# SensorModule.net
KiCad netlist of a schematic drawn in EAGLE
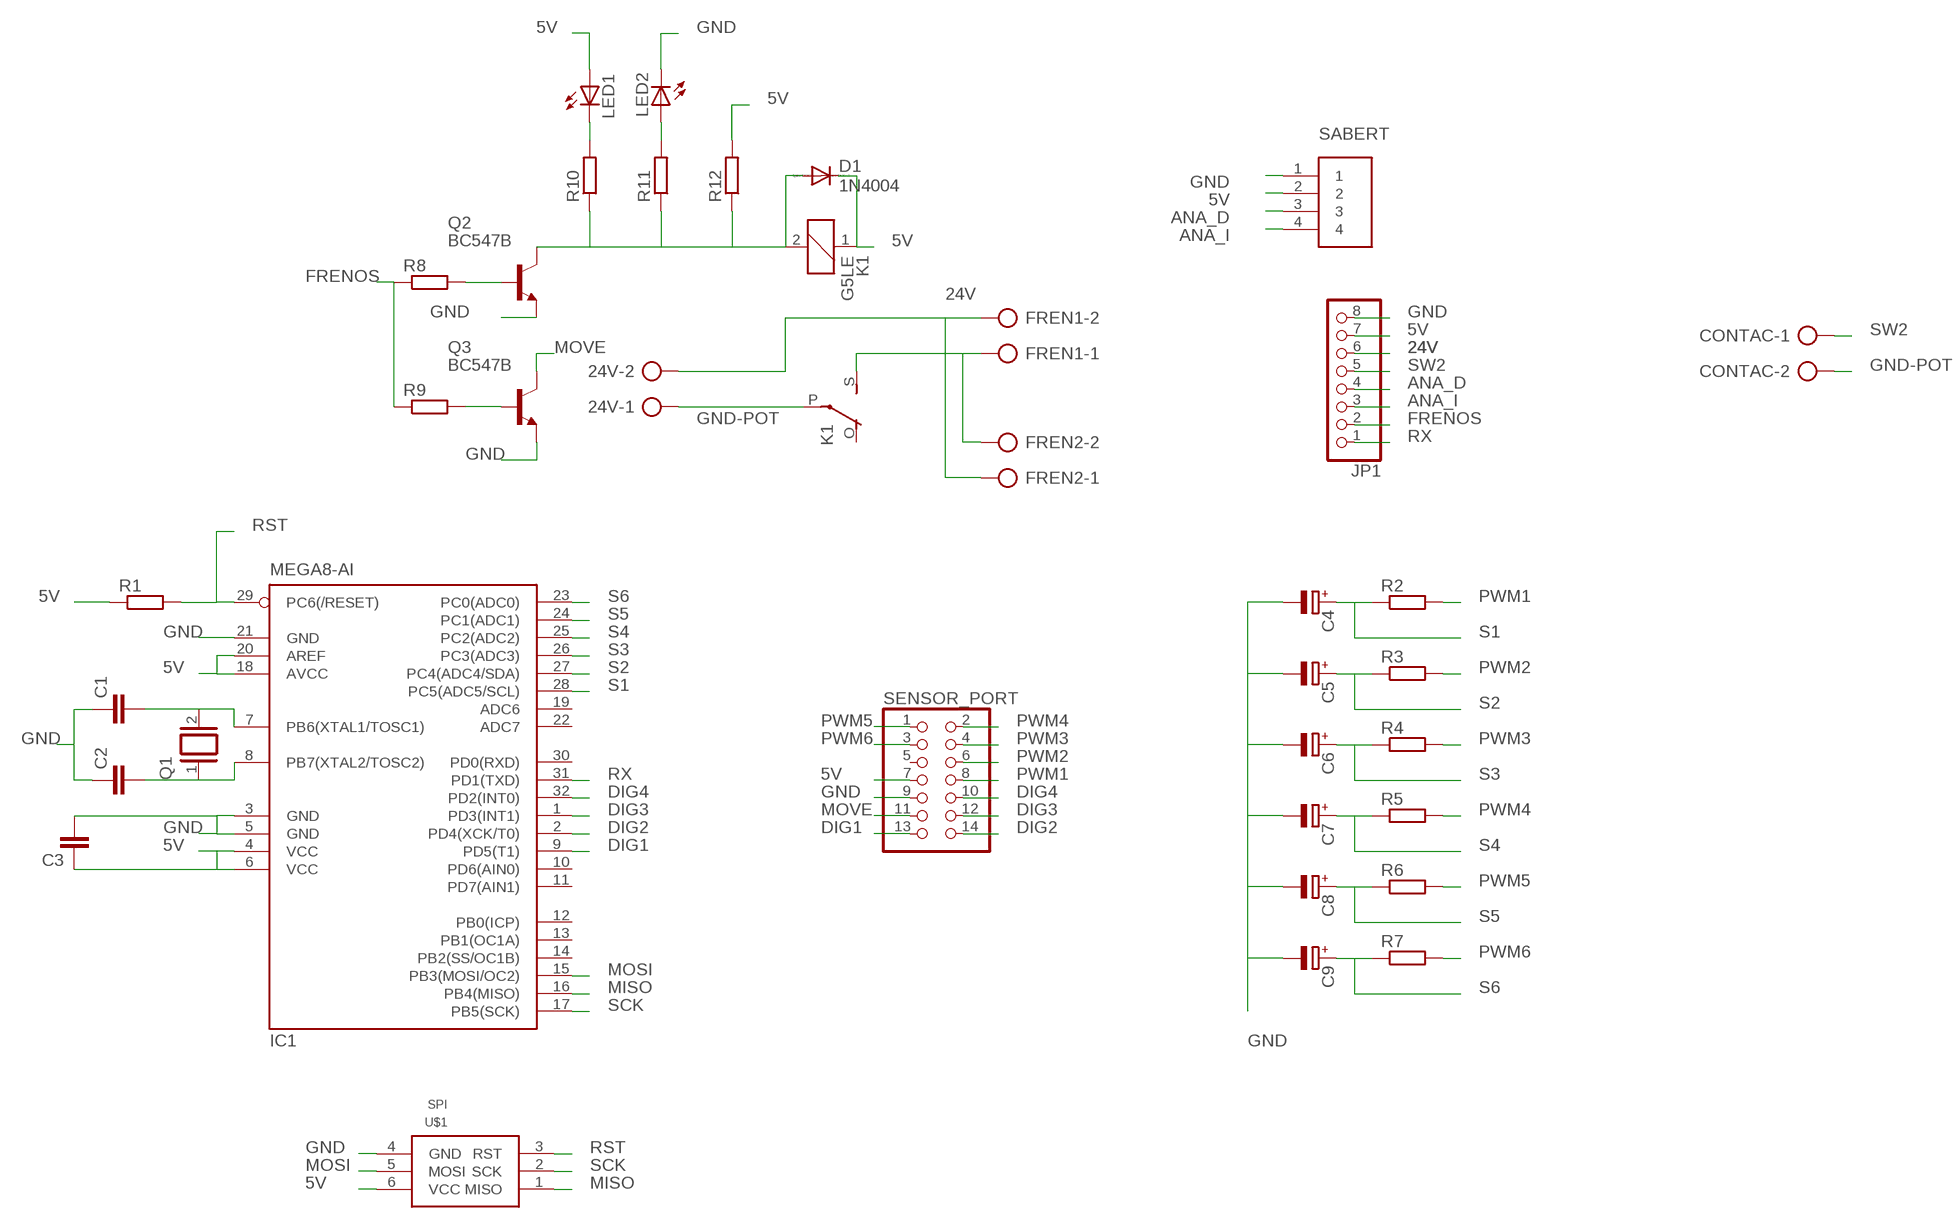
[diagram p0: schematic, sheet 1]

(export (version "E")
  (design (tool "Eeschema 10.0.6"))
  (components
    (comp (ref "24V")
      (value "AK500/2")
      (footprint "eagle-import:AK500_2")
      (libsource (lib "eagle-import") (part "AK500/2"))
    )
    (comp (ref "C1")
      (value "C-EUC0402K")
      (footprint "eagle-import:C0402K")
      (libsource (lib "eagle-import") (part "C-EUC0402K"))
    )
    (comp (ref "C2")
      (value "C-EUC0402K")
      (footprint "eagle-import:C0402K")
      (libsource (lib "eagle-import") (part "C-EUC0402K"))
    )
    (comp (ref "C3")
      (value "C-EUC0402K")
      (footprint "eagle-import:C0402K")
      (libsource (lib "eagle-import") (part "C-EUC0402K"))
    )
    (comp (ref "C4")
      (value "CPOL-EU153CLV-0505")
      (footprint "eagle-import:153CLV-0505")
      (libsource (lib "eagle-import") (part "CPOL-EU153CLV-0505"))
    )
    (comp (ref "C5")
      (value "CPOL-EU153CLV-0505")
      (footprint "eagle-import:153CLV-0505")
      (libsource (lib "eagle-import") (part "CPOL-EU153CLV-0505"))
    )
    (comp (ref "C6")
      (value "CPOL-EU153CLV-0505")
      (footprint "eagle-import:153CLV-0505")
      (libsource (lib "eagle-import") (part "CPOL-EU153CLV-0505"))
    )
    (comp (ref "C7")
      (value "CPOL-EU153CLV-0505")
      (footprint "eagle-import:153CLV-0505")
      (libsource (lib "eagle-import") (part "CPOL-EU153CLV-0505"))
    )
    (comp (ref "C8")
      (value "CPOL-EU153CLV-0505")
      (footprint "eagle-import:153CLV-0505")
      (libsource (lib "eagle-import") (part "CPOL-EU153CLV-0505"))
    )
    (comp (ref "C9")
      (value "CPOL-EU153CLV-0505")
      (footprint "eagle-import:153CLV-0505")
      (libsource (lib "eagle-import") (part "CPOL-EU153CLV-0505"))
    )
    (comp (ref "CONTAC")
      (value "AK500/2")
      (footprint "eagle-import:AK500_2")
      (libsource (lib "eagle-import") (part "AK500/2"))
    )
    (comp (ref "D1")
      (value "1N4004")
      (footprint "eagle-import:DO41-10")
      (libsource (lib "eagle-import") (part "1N4004"))
    )
    (comp (ref "FREN1")
      (value "AK500/2")
      (footprint "eagle-import:AK500_2")
      (libsource (lib "eagle-import") (part "AK500/2"))
    )
    (comp (ref "FREN2")
      (value "AK500/2")
      (footprint "eagle-import:AK500_2")
      (libsource (lib "eagle-import") (part "AK500/2"))
    )
    (comp (ref "IC1")
      (value "MEGA8-AI")
      (footprint "eagle-import:TQFP32-08")
      (fields (field (name "MPN") "ATMEGA8-16AU"))
      (libsource (lib "eagle-import") (part "MEGA8-AI"))
    )
    (comp (ref "JP1")
      (value "PINHD-1X8")
      (footprint "eagle-import:1X08")
      (libsource (lib "eagle-import") (part "PINHD-1X8"))
    )
    (comp (ref "K1")
      (value "G5LE")
      (footprint "eagle-import:G5LE")
      (libsource (lib "eagle-import") (part "G5LE"))
    )
    (comp (ref "LED1")
      (value "LEDCHIP-LED0603")
      (footprint "eagle-import:CHIP-LED0603")
      (libsource (lib "eagle-import") (part "LEDCHIP-LED0603"))
    )
    (comp (ref "LED2")
      (value "LEDCHIP-LED0603")
      (footprint "eagle-import:CHIP-LED0603")
      (libsource (lib "eagle-import") (part "LEDCHIP-LED0603"))
    )
    (comp (ref "Q1")
      (value "XTAL/S")
      (footprint "eagle-import:QS")
      (libsource (lib "eagle-import") (part "XTAL/S"))
    )
    (comp (ref "Q2")
      (value "BC547B")
      (footprint "eagle-import:TO92")
      (libsource (lib "eagle-import") (part "BC547B"))
    )
    (comp (ref "Q3")
      (value "BC547B")
      (footprint "eagle-import:TO92")
      (libsource (lib "eagle-import") (part "BC547B"))
    )
    (comp (ref "R1")
      (value "R-EU_M1206")
      (footprint "eagle-import:M1206")
      (libsource (lib "eagle-import") (part "R-EU_M1206"))
    )
    (comp (ref "R2")
      (value "R-EU_M1206")
      (footprint "eagle-import:M1206")
      (libsource (lib "eagle-import") (part "R-EU_M1206"))
    )
    (comp (ref "R3")
      (value "R-EU_M1206")
      (footprint "eagle-import:M1206")
      (libsource (lib "eagle-import") (part "R-EU_M1206"))
    )
    (comp (ref "R4")
      (value "R-EU_M1206")
      (footprint "eagle-import:M1206")
      (libsource (lib "eagle-import") (part "R-EU_M1206"))
    )
    (comp (ref "R5")
      (value "R-EU_M1206")
      (footprint "eagle-import:M1206")
      (libsource (lib "eagle-import") (part "R-EU_M1206"))
    )
    (comp (ref "R6")
      (value "R-EU_M1206")
      (footprint "eagle-import:M1206")
      (libsource (lib "eagle-import") (part "R-EU_M1206"))
    )
    (comp (ref "R7")
      (value "R-EU_M1206")
      (footprint "eagle-import:M1206")
      (libsource (lib "eagle-import") (part "R-EU_M1206"))
    )
    (comp (ref "R8")
      (value "R-EU_M1206")
      (footprint "eagle-import:M1206")
      (libsource (lib "eagle-import") (part "R-EU_M1206"))
    )
    (comp (ref "R9")
      (value "R-EU_M1206")
      (footprint "eagle-import:M1206")
      (libsource (lib "eagle-import") (part "R-EU_M1206"))
    )
    (comp (ref "R10")
      (value "R-EU_M1206")
      (footprint "eagle-import:M1206")
      (libsource (lib "eagle-import") (part "R-EU_M1206"))
    )
    (comp (ref "R11")
      (value "R-EU_M1206")
      (footprint "eagle-import:M1206")
      (libsource (lib "eagle-import") (part "R-EU_M1206"))
    )
    (comp (ref "R12")
      (value "R-EU_M1206")
      (footprint "eagle-import:M1206")
      (libsource (lib "eagle-import") (part "R-EU_M1206"))
    )
    (comp (ref "SABERT")
      (value "CP2_1X4")
      (footprint "eagle-import:CP2_1X4")
      (libsource (lib "eagle-import") (part "CP2_1X4"))
    )
    (comp (ref "SENSOR_PORT")
      (value "PINHD-2X7")
      (footprint "eagle-import:2X07")
      (libsource (lib "eagle-import") (part "PINHD-2X7"))
    )
    (comp (ref "U$1")
      (value "SPI")
      (footprint "eagle-import:HEAD-2X3")
      (libsource (lib "eagle-import") (part "SPI"))
    )
  )
  (nets
    (net (code "1") (name "/5V") (class "Default")
      (node (ref "C3") (pin "1") (pinfunction "1_1") (pintype "passive"))
      (node (ref "D1") (pin "C") (pinfunction "C_C") (pintype "passive"))
      (node (ref "IC1") (pin "18") (pinfunction "AVCC_18") (pintype "power_in"))
      (node (ref "IC1") (pin "20") (pinfunction "AREF_20") (pintype "passive"))
      (node (ref "IC1") (pin "4") (pinfunction "VCC_4") (pintype "power_in"))
      (node (ref "IC1") (pin "6") (pinfunction "VCC_6") (pintype "power_in"))
      (node (ref "JP1") (pin "7") (pinfunction "7_7") (pintype "passive"))
      (node (ref "K1") (pin "1") (pinfunction "1_1") (pintype "passive"))
      (node (ref "LED1") (pin "A") (pinfunction "A_A") (pintype "passive"))
      (node (ref "R1") (pin "1") (pinfunction "1_1") (pintype "passive"))
      (node (ref "R12") (pin "2") (pinfunction "2_2") (pintype "passive"))
      (node (ref "SABERT") (pin "2") (pinfunction "2_2") (pintype "bidirectional"))
      (node (ref "SENSOR_PORT") (pin "7") (pinfunction "7_7") (pintype "passive"))
      (node (ref "U$1") (pin "6") (pinfunction "VCC_6") (pintype "bidirectional"))
    )
    (net (code "2") (name "/24V") (class "Default")
      (node (ref "24V") (pin "2") (pinfunction "KL_2") (pintype "passive"))
      (node (ref "FREN1") (pin "2") (pinfunction "KL_2") (pintype "passive"))
      (node (ref "FREN2") (pin "1") (pinfunction "KL_1") (pintype "passive"))
      (node (ref "JP1") (pin "6") (pinfunction "6_6") (pintype "passive"))
    )
    (net (code "3") (name "/ANA_D") (class "Default")
      (node (ref "JP1") (pin "4") (pinfunction "4_4") (pintype "passive"))
      (node (ref "SABERT") (pin "3") (pinfunction "3_3") (pintype "bidirectional"))
    )
    (net (code "4") (name "/ANA_I") (class "Default")
      (node (ref "JP1") (pin "3") (pinfunction "3_3") (pintype "passive"))
      (node (ref "SABERT") (pin "4") (pinfunction "4_4") (pintype "bidirectional"))
    )
    (net (code "5") (name "/DIG1") (class "Default")
      (node (ref "IC1") (pin "9") (pinfunction "PD5(T1)_9") (pintype "bidirectional"))
      (node (ref "SENSOR_PORT") (pin "13") (pinfunction "13_13") (pintype "passive"))
    )
    (net (code "6") (name "/DIG2") (class "Default")
      (node (ref "IC1") (pin "2") (pinfunction "PD4(XCK/T0)_2") (pintype "bidirectional"))
      (node (ref "SENSOR_PORT") (pin "14") (pinfunction "14_14") (pintype "passive"))
    )
    (net (code "7") (name "/DIG3") (class "Default")
      (node (ref "IC1") (pin "1") (pinfunction "PD3(INT1)_1") (pintype "bidirectional"))
      (node (ref "SENSOR_PORT") (pin "12") (pinfunction "12_12") (pintype "passive"))
    )
    (net (code "8") (name "/DIG4") (class "Default")
      (node (ref "IC1") (pin "32") (pinfunction "PD2(INT0)_32") (pintype "bidirectional"))
      (node (ref "SENSOR_PORT") (pin "10") (pinfunction "10_10") (pintype "passive"))
    )
    (net (code "9") (name "/FRENOS") (class "Default")
      (node (ref "JP1") (pin "2") (pinfunction "2_2") (pintype "passive"))
      (node (ref "R8") (pin "1") (pinfunction "1_1") (pintype "passive"))
      (node (ref "R9") (pin "1") (pinfunction "1_1") (pintype "passive"))
    )
    (net (code "10") (name "/GND") (class "Default")
      (node (ref "C1") (pin "1") (pinfunction "1_1") (pintype "passive"))
      (node (ref "C2") (pin "1") (pinfunction "1_1") (pintype "passive"))
      (node (ref "C3") (pin "2") (pinfunction "2_2") (pintype "passive"))
      (node (ref "C4") (pin "-") (pinfunction "-_-") (pintype "passive"))
      (node (ref "C5") (pin "-") (pinfunction "-_-") (pintype "passive"))
      (node (ref "C6") (pin "-") (pinfunction "-_-") (pintype "passive"))
      (node (ref "C7") (pin "-") (pinfunction "-_-") (pintype "passive"))
      (node (ref "C8") (pin "-") (pinfunction "-_-") (pintype "passive"))
      (node (ref "C9") (pin "-") (pinfunction "-_-") (pintype "passive"))
      (node (ref "IC1") (pin "21") (pinfunction "GND_21") (pintype "power_in"))
      (node (ref "IC1") (pin "3") (pinfunction "GND_3") (pintype "power_in"))
      (node (ref "IC1") (pin "5") (pinfunction "GND_5") (pintype "power_in"))
      (node (ref "JP1") (pin "8") (pinfunction "8_8") (pintype "passive"))
      (node (ref "LED2") (pin "C") (pinfunction "C_C") (pintype "passive"))
      (node (ref "Q2") (pin "1") (pinfunction "E_1") (pintype "passive"))
      (node (ref "Q3") (pin "1") (pinfunction "E_1") (pintype "passive"))
      (node (ref "SABERT") (pin "1") (pinfunction "1_1") (pintype "bidirectional"))
      (node (ref "SENSOR_PORT") (pin "9") (pinfunction "9_9") (pintype "passive"))
      (node (ref "U$1") (pin "4") (pinfunction "GND_4") (pintype "bidirectional"))
    )
    (net (code "11") (name "/GND-POT") (class "Default")
      (node (ref "24V") (pin "1") (pinfunction "KL_1") (pintype "passive"))
      (node (ref "CONTAC") (pin "2") (pinfunction "KL_2") (pintype "passive"))
      (node (ref "K1") (pin "P") (pinfunction "P_P") (pintype "passive"))
    )
    (net (code "12") (name "/MISO") (class "Default")
      (node (ref "IC1") (pin "16") (pinfunction "PB4(MISO)_16") (pintype "bidirectional"))
      (node (ref "U$1") (pin "1") (pinfunction "MISO_1") (pintype "bidirectional"))
    )
    (net (code "13") (name "/MOSI") (class "Default")
      (node (ref "IC1") (pin "15") (pinfunction "PB3(MOSI/OC2)_15") (pintype "bidirectional"))
      (node (ref "U$1") (pin "5") (pinfunction "MOSI_5") (pintype "bidirectional"))
    )
    (net (code "14") (name "/MOVE") (class "Default")
      (node (ref "Q3") (pin "3") (pinfunction "C_3") (pintype "passive"))
      (node (ref "SENSOR_PORT") (pin "11") (pinfunction "11_11") (pintype "passive"))
    )
    (net (code "15") (name "/PWM1") (class "Default")
      (node (ref "R2") (pin "2") (pinfunction "2_2") (pintype "passive"))
      (node (ref "SENSOR_PORT") (pin "8") (pinfunction "8_8") (pintype "passive"))
    )
    (net (code "16") (name "/PWM2") (class "Default")
      (node (ref "R3") (pin "2") (pinfunction "2_2") (pintype "passive"))
      (node (ref "SENSOR_PORT") (pin "6") (pinfunction "6_6") (pintype "passive"))
    )
    (net (code "17") (name "/PWM3") (class "Default")
      (node (ref "R4") (pin "2") (pinfunction "2_2") (pintype "passive"))
      (node (ref "SENSOR_PORT") (pin "4") (pinfunction "4_4") (pintype "passive"))
    )
    (net (code "18") (name "/PWM4") (class "Default")
      (node (ref "R5") (pin "2") (pinfunction "2_2") (pintype "passive"))
      (node (ref "SENSOR_PORT") (pin "2") (pinfunction "2_2") (pintype "passive"))
    )
    (net (code "19") (name "/PWM5") (class "Default")
      (node (ref "R6") (pin "2") (pinfunction "2_2") (pintype "passive"))
      (node (ref "SENSOR_PORT") (pin "1") (pinfunction "1_1") (pintype "passive"))
    )
    (net (code "20") (name "/PWM6") (class "Default")
      (node (ref "R7") (pin "2") (pinfunction "2_2") (pintype "passive"))
      (node (ref "SENSOR_PORT") (pin "3") (pinfunction "3_3") (pintype "passive"))
    )
    (net (code "21") (name "/RST") (class "Default")
      (node (ref "IC1") (pin "29") (pinfunction "PC6(/RESET)_29") (pintype "bidirectional"))
      (node (ref "R1") (pin "2") (pinfunction "2_2") (pintype "passive"))
      (node (ref "U$1") (pin "3") (pinfunction "RST_3") (pintype "bidirectional"))
    )
    (net (code "22") (name "/RX") (class "Default")
      (node (ref "IC1") (pin "31") (pinfunction "PD1(TXD)_31") (pintype "bidirectional"))
      (node (ref "JP1") (pin "1") (pinfunction "1_1") (pintype "passive"))
    )
    (net (code "23") (name "/S1") (class "Default")
      (node (ref "C4") (pin "+") (pinfunction "+_+") (pintype "passive"))
      (node (ref "IC1") (pin "28") (pinfunction "PC5(ADC5/SCL)_28") (pintype "bidirectional"))
      (node (ref "R2") (pin "1") (pinfunction "1_1") (pintype "passive"))
    )
    (net (code "24") (name "/S2") (class "Default")
      (node (ref "C5") (pin "+") (pinfunction "+_+") (pintype "passive"))
      (node (ref "IC1") (pin "27") (pinfunction "PC4(ADC4/SDA)_27") (pintype "bidirectional"))
      (node (ref "R3") (pin "1") (pinfunction "1_1") (pintype "passive"))
    )
    (net (code "25") (name "/S3") (class "Default")
      (node (ref "C6") (pin "+") (pinfunction "+_+") (pintype "passive"))
      (node (ref "IC1") (pin "26") (pinfunction "PC3(ADC3)_26") (pintype "bidirectional"))
      (node (ref "R4") (pin "1") (pinfunction "1_1") (pintype "passive"))
    )
    (net (code "26") (name "/S4") (class "Default")
      (node (ref "C7") (pin "+") (pinfunction "+_+") (pintype "passive"))
      (node (ref "IC1") (pin "25") (pinfunction "PC2(ADC2)_25") (pintype "bidirectional"))
      (node (ref "R5") (pin "1") (pinfunction "1_1") (pintype "passive"))
    )
    (net (code "27") (name "/S5") (class "Default")
      (node (ref "C8") (pin "+") (pinfunction "+_+") (pintype "passive"))
      (node (ref "IC1") (pin "24") (pinfunction "PC1(ADC1)_24") (pintype "bidirectional"))
      (node (ref "R6") (pin "1") (pinfunction "1_1") (pintype "passive"))
    )
    (net (code "28") (name "/S6") (class "Default")
      (node (ref "C9") (pin "+") (pinfunction "+_+") (pintype "passive"))
      (node (ref "IC1") (pin "23") (pinfunction "PC0(ADC0)_23") (pintype "bidirectional"))
      (node (ref "R7") (pin "1") (pinfunction "1_1") (pintype "passive"))
    )
    (net (code "29") (name "/SCK") (class "Default")
      (node (ref "IC1") (pin "17") (pinfunction "PB5(SCK)_17") (pintype "bidirectional"))
      (node (ref "U$1") (pin "2") (pinfunction "SCK_2") (pintype "bidirectional"))
    )
    (net (code "30") (name "/SW2") (class "Default")
      (node (ref "CONTAC") (pin "1") (pinfunction "KL_1") (pintype "passive"))
      (node (ref "JP1") (pin "5") (pinfunction "5_5") (pintype "passive"))
    )
    (net (code "31") (name "Net-(FREN1A-KL)") (class "Default")
      (node (ref "FREN1") (pin "1") (pinfunction "KL_1") (pintype "passive"))
      (node (ref "FREN2") (pin "2") (pinfunction "KL_2") (pintype "passive"))
      (node (ref "K1") (pin "S") (pinfunction "S_S") (pintype "passive"))
    )
    (net (code "32") (name "Net-(IC1-PB6(XTAL1{slash}TOSC1))") (class "Default")
      (node (ref "C1") (pin "2") (pinfunction "2_2") (pintype "passive"))
      (node (ref "IC1") (pin "7") (pinfunction "PB6(XTAL1/TOSC1)_7") (pintype "bidirectional"))
      (node (ref "Q1") (pin "2") (pinfunction "2_2") (pintype "passive"))
    )
    (net (code "33") (name "Net-(IC1-PB7(XTAL2{slash}TOSC2))") (class "Default")
      (node (ref "C2") (pin "2") (pinfunction "2_2") (pintype "passive"))
      (node (ref "IC1") (pin "8") (pinfunction "PB7(XTAL2/TOSC2)_8") (pintype "bidirectional"))
      (node (ref "Q1") (pin "1") (pinfunction "1_1") (pintype "passive"))
    )
    (net (code "34") (name "Net-(LED1-PadC)") (class "Default")
      (node (ref "LED1") (pin "C") (pinfunction "C_C") (pintype "passive"))
      (node (ref "R10") (pin "2") (pinfunction "2_2") (pintype "passive"))
    )
    (net (code "35") (name "Net-(LED2-PadA)") (class "Default")
      (node (ref "LED2") (pin "A") (pinfunction "A_A") (pintype "passive"))
      (node (ref "R11") (pin "2") (pinfunction "2_2") (pintype "passive"))
    )
    (net (code "36") (name "Net-(Q2-B)") (class "Default")
      (node (ref "Q2") (pin "2") (pinfunction "B_2") (pintype "passive"))
      (node (ref "R8") (pin "2") (pinfunction "2_2") (pintype "passive"))
    )
    (net (code "37") (name "Net-(Q2-C)") (class "Default")
      (node (ref "D1") (pin "A") (pinfunction "A_A") (pintype "passive"))
      (node (ref "K1") (pin "2") (pinfunction "2_2") (pintype "passive"))
      (node (ref "Q2") (pin "3") (pinfunction "C_3") (pintype "passive"))
      (node (ref "R10") (pin "1") (pinfunction "1_1") (pintype "passive"))
      (node (ref "R11") (pin "1") (pinfunction "1_1") (pintype "passive"))
      (node (ref "R12") (pin "1") (pinfunction "1_1") (pintype "passive"))
    )
    (net (code "38") (name "Net-(Q3-B)") (class "Default")
      (node (ref "Q3") (pin "2") (pinfunction "B_2") (pintype "passive"))
      (node (ref "R9") (pin "2") (pinfunction "2_2") (pintype "passive"))
    )
    (net (code "39") (name "unconnected-(IC1-ADC6-Pad19)") (class "Default")
      (node (ref "IC1") (pin "19") (pinfunction "ADC6_19") (pintype "bidirectional"))
    )
    (net (code "40") (name "unconnected-(IC1-ADC7-Pad22)") (class "Default")
      (node (ref "IC1") (pin "22") (pinfunction "ADC7_22") (pintype "bidirectional"))
    )
    (net (code "41") (name "unconnected-(IC1-PB0(ICP)-Pad12)") (class "Default")
      (node (ref "IC1") (pin "12") (pinfunction "PB0(ICP)_12") (pintype "bidirectional"))
    )
    (net (code "42") (name "unconnected-(IC1-PB1(OC1A)-Pad13)") (class "Default")
      (node (ref "IC1") (pin "13") (pinfunction "PB1(OC1A)_13") (pintype "bidirectional"))
    )
    (net (code "43") (name "unconnected-(IC1-PB2(SS{slash}OC1B)-Pad14)") (class "Default")
      (node (ref "IC1") (pin "14") (pinfunction "PB2(SS/OC1B)_14") (pintype "bidirectional"))
    )
    (net (code "44") (name "unconnected-(IC1-PD0(RXD)-Pad30)") (class "Default")
      (node (ref "IC1") (pin "30") (pinfunction "PD0(RXD)_30") (pintype "bidirectional"))
    )
    (net (code "45") (name "unconnected-(IC1-PD6(AIN0)-Pad10)") (class "Default")
      (node (ref "IC1") (pin "10") (pinfunction "PD6(AIN0)_10") (pintype "bidirectional"))
    )
    (net (code "46") (name "unconnected-(IC1-PD7(AIN1)-Pad11)") (class "Default")
      (node (ref "IC1") (pin "11") (pinfunction "PD7(AIN1)_11") (pintype "bidirectional"))
    )
    (net (code "47") (name "unconnected-(K1-PadO)") (class "Default")
      (node (ref "K1") (pin "O") (pinfunction "O_O") (pintype "passive"))
    )
    (net (code "48") (name "unconnected-(SENSOR_PORT-Pad5)") (class "Default")
      (node (ref "SENSOR_PORT") (pin "5") (pinfunction "5_5") (pintype "passive"))
    )
  )
)
